# DIYTIL311_v1_2.net
KiCad netlist of a schematic drawn in EAGLE
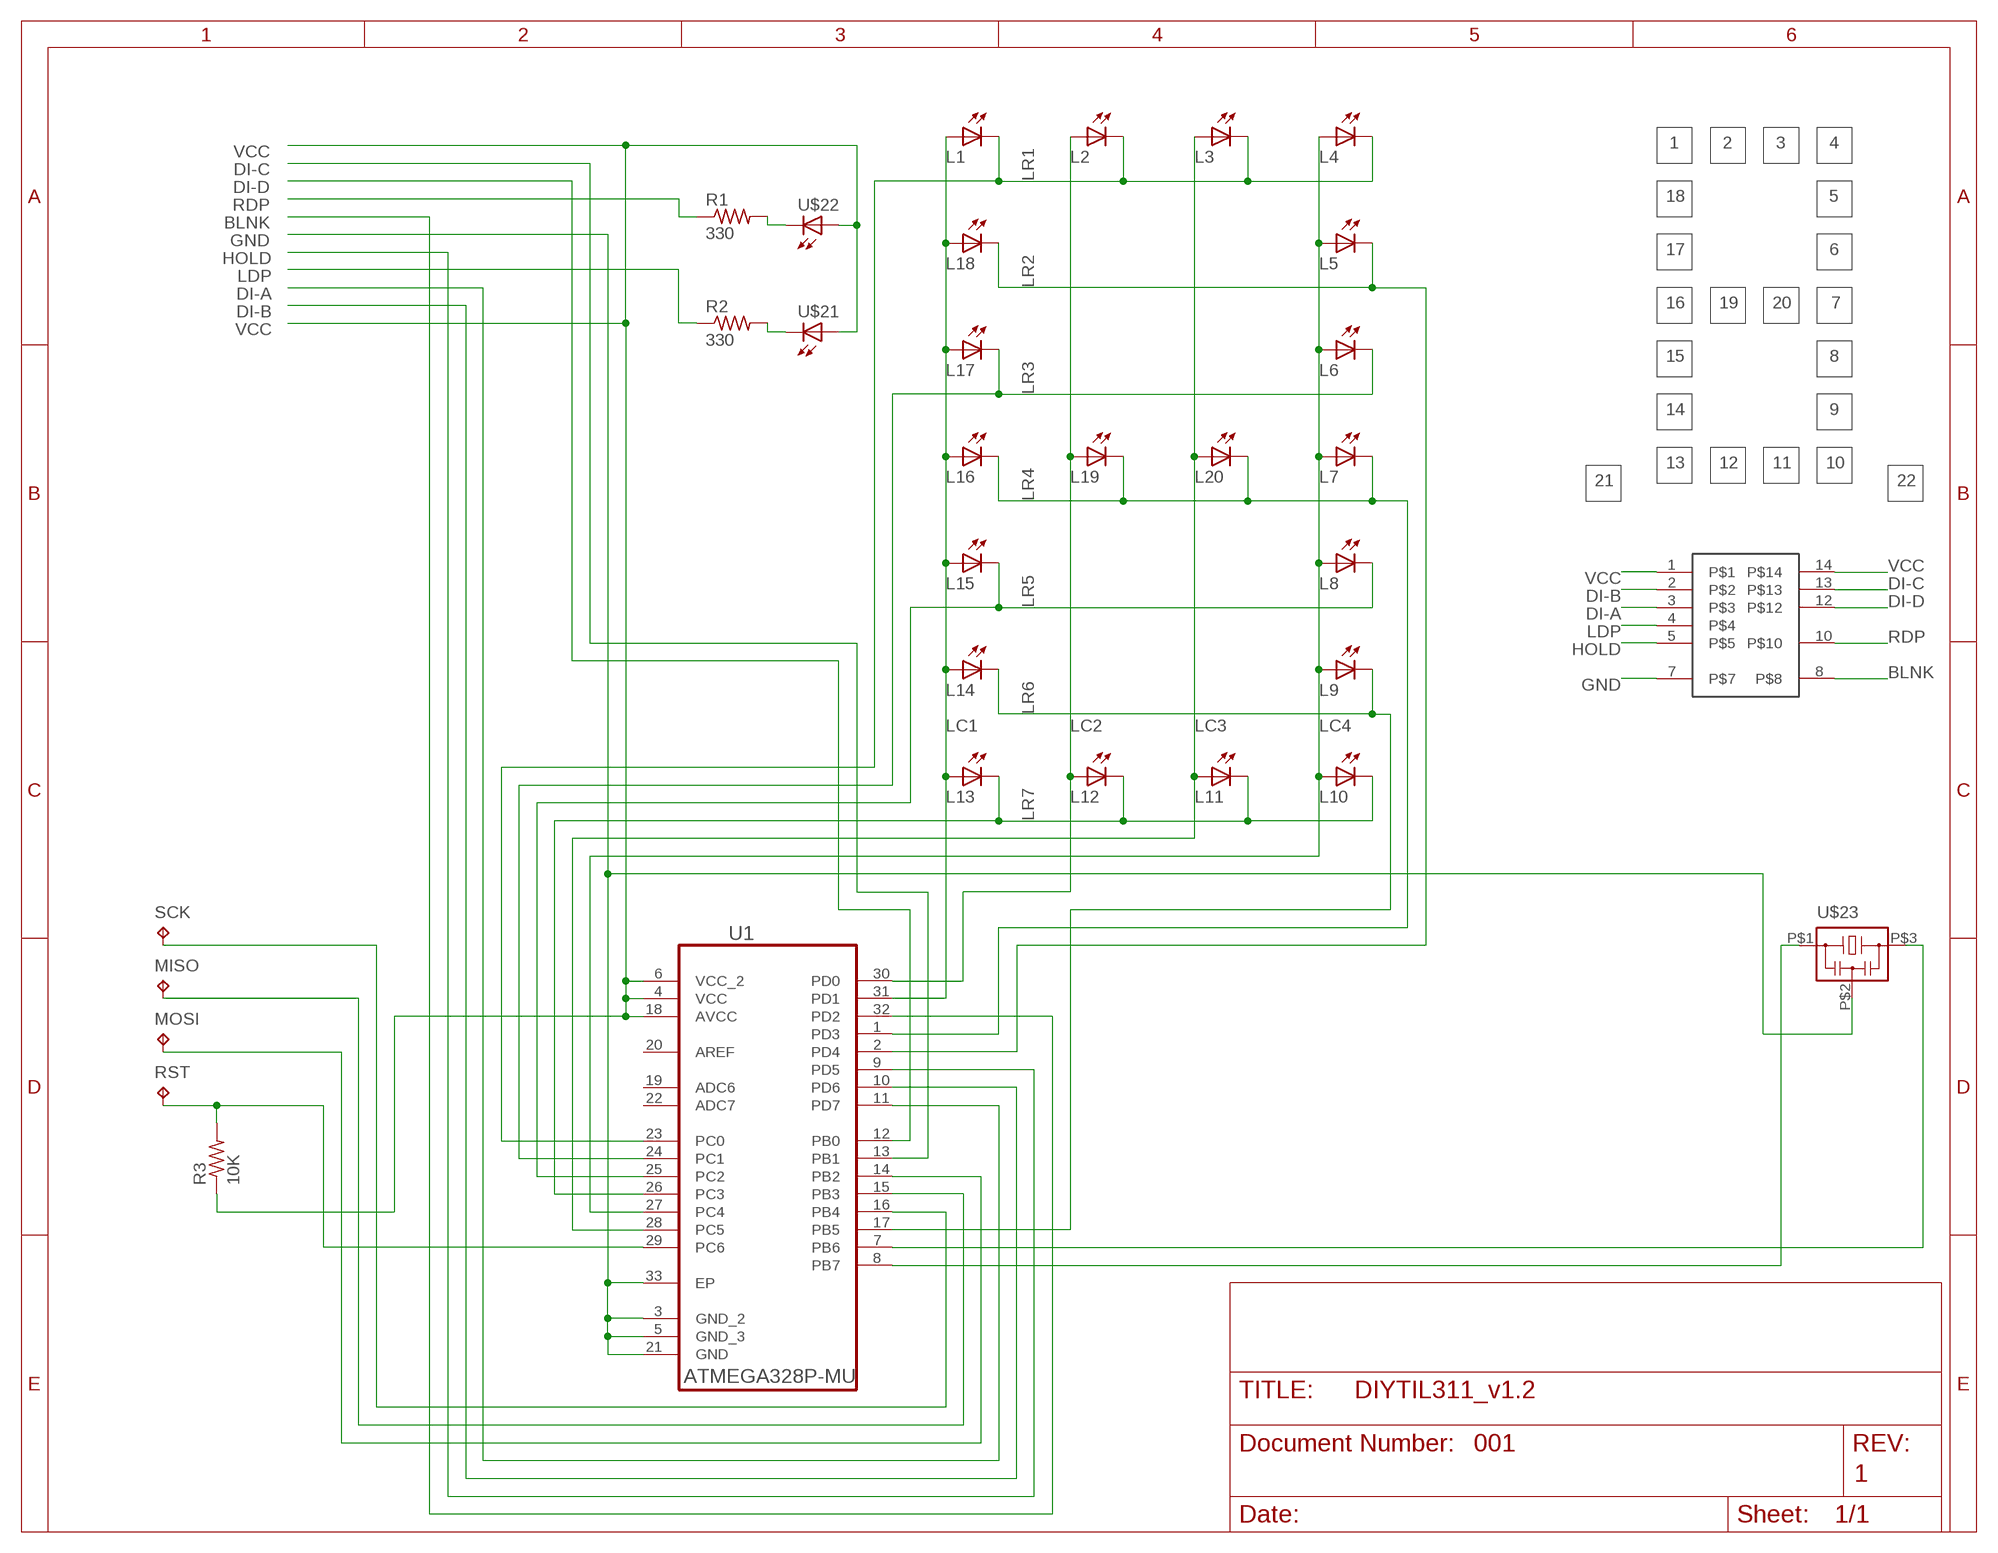
[diagram p0: schematic, sheet 1]

(export (version "E")
  (design (tool "Eeschema 10.0.6"))
  (components
    (comp (ref "L1")
      (value "0201.LED0201")
      (footprint "eagle-import:LEDC0603X33")
      (libsource (lib "eagle-import") (part "0201.LED0201"))
    )
    (comp (ref "L2")
      (value "0201.LED0201")
      (footprint "eagle-import:LEDC0603X33")
      (libsource (lib "eagle-import") (part "0201.LED0201"))
    )
    (comp (ref "L3")
      (value "0201.LED0201")
      (footprint "eagle-import:LEDC0603X33")
      (libsource (lib "eagle-import") (part "0201.LED0201"))
    )
    (comp (ref "L4")
      (value "0201.LED0201")
      (footprint "eagle-import:LEDC0603X33")
      (libsource (lib "eagle-import") (part "0201.LED0201"))
    )
    (comp (ref "L5")
      (value "0201.LED0201")
      (footprint "eagle-import:LEDC0603X33")
      (libsource (lib "eagle-import") (part "0201.LED0201"))
    )
    (comp (ref "L6")
      (value "0201.LED0201")
      (footprint "eagle-import:LEDC0603X33")
      (libsource (lib "eagle-import") (part "0201.LED0201"))
    )
    (comp (ref "L7")
      (value "0201.LED0201")
      (footprint "eagle-import:LEDC0603X33")
      (libsource (lib "eagle-import") (part "0201.LED0201"))
    )
    (comp (ref "L8")
      (value "0201.LED0201")
      (footprint "eagle-import:LEDC0603X33")
      (libsource (lib "eagle-import") (part "0201.LED0201"))
    )
    (comp (ref "L9")
      (value "0201.LED0201")
      (footprint "eagle-import:LEDC0603X33")
      (libsource (lib "eagle-import") (part "0201.LED0201"))
    )
    (comp (ref "L10")
      (value "0201.LED0201")
      (footprint "eagle-import:LEDC0603X33")
      (libsource (lib "eagle-import") (part "0201.LED0201"))
    )
    (comp (ref "L11")
      (value "0201.LED0201")
      (footprint "eagle-import:LEDC0603X33")
      (libsource (lib "eagle-import") (part "0201.LED0201"))
    )
    (comp (ref "L12")
      (value "0201.LED0201")
      (footprint "eagle-import:LEDC0603X33")
      (libsource (lib "eagle-import") (part "0201.LED0201"))
    )
    (comp (ref "L13")
      (value "0201.LED0201")
      (footprint "eagle-import:LEDC0603X33")
      (libsource (lib "eagle-import") (part "0201.LED0201"))
    )
    (comp (ref "L14")
      (value "0201.LED0201")
      (footprint "eagle-import:LEDC0603X33")
      (libsource (lib "eagle-import") (part "0201.LED0201"))
    )
    (comp (ref "L15")
      (value "0201.LED0201")
      (footprint "eagle-import:LEDC0603X33")
      (libsource (lib "eagle-import") (part "0201.LED0201"))
    )
    (comp (ref "L16")
      (value "0201.LED0201")
      (footprint "eagle-import:LEDC0603X33")
      (libsource (lib "eagle-import") (part "0201.LED0201"))
    )
    (comp (ref "L17")
      (value "0201.LED0201")
      (footprint "eagle-import:LEDC0603X33")
      (libsource (lib "eagle-import") (part "0201.LED0201"))
    )
    (comp (ref "L18")
      (value "0201.LED0201")
      (footprint "eagle-import:LEDC0603X33")
      (libsource (lib "eagle-import") (part "0201.LED0201"))
    )
    (comp (ref "L19")
      (value "0201.LED0201")
      (footprint "eagle-import:LEDC0603X33")
      (libsource (lib "eagle-import") (part "0201.LED0201"))
    )
    (comp (ref "L20")
      (value "0201.LED0201")
      (footprint "eagle-import:LEDC0603X33")
      (libsource (lib "eagle-import") (part "0201.LED0201"))
    )
    (comp (ref "MISO")
      (value "TPB1,27")
      (footprint "eagle-import:B1,27")
      (libsource (lib "eagle-import") (part "TPB1,27"))
    )
    (comp (ref "MOSI")
      (value "TPB1,27")
      (footprint "eagle-import:B1,27")
      (libsource (lib "eagle-import") (part "TPB1,27"))
    )
    (comp (ref "R1")
      (value "330")
      (footprint "eagle-import:R0201")
      (libsource (lib "eagle-import") (part "R-US_R0201"))
    )
    (comp (ref "R2")
      (value "330")
      (footprint "eagle-import:R0201")
      (libsource (lib "eagle-import") (part "R-US_R0201"))
    )
    (comp (ref "R3")
      (value "10K")
      (footprint "eagle-import:R0201")
      (libsource (lib "eagle-import") (part "R-US_R0201"))
    )
    (comp (ref "RST")
      (value "TPB1,27")
      (footprint "eagle-import:B1,27")
      (libsource (lib "eagle-import") (part "TPB1,27"))
    )
    (comp (ref "SCK")
      (value "TPB1,27")
      (footprint "eagle-import:B1,27")
      (libsource (lib "eagle-import") (part "TPB1,27"))
    )
    (comp (ref "U$21")
      (value "0201.LED0201")
      (footprint "eagle-import:LEDC0603X33")
      (libsource (lib "eagle-import") (part "0201.LED0201"))
    )
    (comp (ref "U$22")
      (value "0201.LED0201")
      (footprint "eagle-import:LEDC0603X33")
      (libsource (lib "eagle-import") (part "0201.LED0201"))
    )
    (comp (ref "U$23")
      (value "CSTNE16M0V53Z000R0")
      (footprint "eagle-import:MFF")
      (libsource (lib "eagle-import") (part "CSTNE16M0V53Z000R0"))
    )
    (comp (ref "U$24")
      (value "TIL311DIP")
      (footprint "eagle-import:TIL311DIP_FOOTPRINT")
      (libsource (lib "eagle-import") (part "TIL311DIP"))
    )
    (comp (ref "U1")
      (value "ATMEGA328P-MU")
      (footprint "eagle-import:QFN50P500X500X100-33N")
      (libsource (lib "eagle-import") (part "ATMEGA328P-MU"))
    )
  )
  (nets
    (net (code "1") (name "/BLNK") (class "Default")
      (node (ref "U$24") (pin "8") (pinfunction "P$8_8") (pintype "bidirectional"))
      (node (ref "U1") (pin "32") (pinfunction "PD2_32") (pintype "bidirectional"))
    )
    (net (code "2") (name "/DI-A") (class "Default")
      (node (ref "U$24") (pin "3") (pinfunction "P$3_3") (pintype "bidirectional"))
      (node (ref "U1") (pin "11") (pinfunction "PD7_11") (pintype "bidirectional"))
    )
    (net (code "3") (name "/DI-B") (class "Default")
      (node (ref "U$24") (pin "2") (pinfunction "P$2_2") (pintype "bidirectional"))
      (node (ref "U1") (pin "10") (pinfunction "PD6_10") (pintype "bidirectional"))
    )
    (net (code "4") (name "/DI-C") (class "Default")
      (node (ref "U$24") (pin "13") (pinfunction "P$13_13") (pintype "bidirectional"))
      (node (ref "U1") (pin "13") (pinfunction "PB1_13") (pintype "bidirectional"))
    )
    (net (code "5") (name "/DI-D") (class "Default")
      (node (ref "U$24") (pin "12") (pinfunction "P$12_12") (pintype "bidirectional"))
      (node (ref "U1") (pin "12") (pinfunction "PB0_12") (pintype "bidirectional"))
    )
    (net (code "6") (name "/GND") (class "Default")
      (node (ref "U$23") (pin "P$2") (pinfunction "2_P$2") (pintype "passive"))
      (node (ref "U$24") (pin "7") (pinfunction "P$7_7") (pintype "bidirectional"))
      (node (ref "U1") (pin "21") (pinfunction "GND_21") (pintype "passive"))
      (node (ref "U1") (pin "3") (pinfunction "GND_2_3") (pintype "passive"))
      (node (ref "U1") (pin "33") (pinfunction "EP_33") (pintype "passive"))
      (node (ref "U1") (pin "5") (pinfunction "GND_3_5") (pintype "passive"))
    )
    (net (code "7") (name "/HOLD") (class "Default")
      (node (ref "U$24") (pin "5") (pinfunction "P$5_5") (pintype "bidirectional"))
      (node (ref "U1") (pin "9") (pinfunction "PD5_9") (pintype "bidirectional"))
    )
    (net (code "8") (name "/LC1") (class "Default")
      (node (ref "L1") (pin "1") (pinfunction "A_1") (pintype "passive"))
      (node (ref "L13") (pin "1") (pinfunction "A_1") (pintype "passive"))
      (node (ref "L14") (pin "1") (pinfunction "A_1") (pintype "passive"))
      (node (ref "L15") (pin "1") (pinfunction "A_1") (pintype "passive"))
      (node (ref "L16") (pin "1") (pinfunction "A_1") (pintype "passive"))
      (node (ref "L17") (pin "1") (pinfunction "A_1") (pintype "passive"))
      (node (ref "L18") (pin "1") (pinfunction "A_1") (pintype "passive"))
      (node (ref "U1") (pin "31") (pinfunction "PD1_31") (pintype "bidirectional"))
    )
    (net (code "9") (name "/LC2") (class "Default")
      (node (ref "L12") (pin "1") (pinfunction "A_1") (pintype "passive"))
      (node (ref "L19") (pin "1") (pinfunction "A_1") (pintype "passive"))
      (node (ref "L2") (pin "1") (pinfunction "A_1") (pintype "passive"))
      (node (ref "U1") (pin "30") (pinfunction "PD0_30") (pintype "bidirectional"))
    )
    (net (code "10") (name "/LC3") (class "Default")
      (node (ref "L11") (pin "1") (pinfunction "A_1") (pintype "passive"))
      (node (ref "L20") (pin "1") (pinfunction "A_1") (pintype "passive"))
      (node (ref "L3") (pin "1") (pinfunction "A_1") (pintype "passive"))
      (node (ref "U1") (pin "28") (pinfunction "PC5_28") (pintype "bidirectional"))
    )
    (net (code "11") (name "/LC4") (class "Default")
      (node (ref "L10") (pin "1") (pinfunction "A_1") (pintype "passive"))
      (node (ref "L4") (pin "1") (pinfunction "A_1") (pintype "passive"))
      (node (ref "L5") (pin "1") (pinfunction "A_1") (pintype "passive"))
      (node (ref "L6") (pin "1") (pinfunction "A_1") (pintype "passive"))
      (node (ref "L7") (pin "1") (pinfunction "A_1") (pintype "passive"))
      (node (ref "L8") (pin "1") (pinfunction "A_1") (pintype "passive"))
      (node (ref "L9") (pin "1") (pinfunction "A_1") (pintype "passive"))
      (node (ref "U1") (pin "27") (pinfunction "PC4_27") (pintype "bidirectional"))
    )
    (net (code "12") (name "/LDP") (class "Default")
      (node (ref "R2") (pin "1") (pinfunction "1_1") (pintype "passive"))
      (node (ref "U$24") (pin "4") (pinfunction "P$4_4") (pintype "bidirectional"))
    )
    (net (code "13") (name "/LR1") (class "Default")
      (node (ref "L1") (pin "2") (pinfunction "C_2") (pintype "passive"))
      (node (ref "L2") (pin "2") (pinfunction "C_2") (pintype "passive"))
      (node (ref "L3") (pin "2") (pinfunction "C_2") (pintype "passive"))
      (node (ref "L4") (pin "2") (pinfunction "C_2") (pintype "passive"))
      (node (ref "U1") (pin "23") (pinfunction "PC0_23") (pintype "bidirectional"))
    )
    (net (code "14") (name "/LR2") (class "Default")
      (node (ref "L18") (pin "2") (pinfunction "C_2") (pintype "passive"))
      (node (ref "L5") (pin "2") (pinfunction "C_2") (pintype "passive"))
      (node (ref "U1") (pin "2") (pinfunction "PD4_2") (pintype "bidirectional"))
    )
    (net (code "15") (name "/LR3") (class "Default")
      (node (ref "L17") (pin "2") (pinfunction "C_2") (pintype "passive"))
      (node (ref "L6") (pin "2") (pinfunction "C_2") (pintype "passive"))
      (node (ref "U1") (pin "24") (pinfunction "PC1_24") (pintype "bidirectional"))
    )
    (net (code "16") (name "/LR4") (class "Default")
      (node (ref "L16") (pin "2") (pinfunction "C_2") (pintype "passive"))
      (node (ref "L19") (pin "2") (pinfunction "C_2") (pintype "passive"))
      (node (ref "L20") (pin "2") (pinfunction "C_2") (pintype "passive"))
      (node (ref "L7") (pin "2") (pinfunction "C_2") (pintype "passive"))
      (node (ref "U1") (pin "1") (pinfunction "PD3_1") (pintype "bidirectional"))
    )
    (net (code "17") (name "/LR5") (class "Default")
      (node (ref "L15") (pin "2") (pinfunction "C_2") (pintype "passive"))
      (node (ref "L8") (pin "2") (pinfunction "C_2") (pintype "passive"))
      (node (ref "U1") (pin "25") (pinfunction "PC2_25") (pintype "bidirectional"))
    )
    (net (code "18") (name "/LR6") (class "Default")
      (node (ref "L14") (pin "2") (pinfunction "C_2") (pintype "passive"))
      (node (ref "L9") (pin "2") (pinfunction "C_2") (pintype "passive"))
      (node (ref "U1") (pin "17") (pinfunction "PB5_17") (pintype "bidirectional"))
    )
    (net (code "19") (name "/LR7") (class "Default")
      (node (ref "L10") (pin "2") (pinfunction "C_2") (pintype "passive"))
      (node (ref "L11") (pin "2") (pinfunction "C_2") (pintype "passive"))
      (node (ref "L12") (pin "2") (pinfunction "C_2") (pintype "passive"))
      (node (ref "L13") (pin "2") (pinfunction "C_2") (pintype "passive"))
      (node (ref "U1") (pin "26") (pinfunction "PC3_26") (pintype "bidirectional"))
    )
    (net (code "20") (name "/RDP") (class "Default")
      (node (ref "R1") (pin "1") (pinfunction "1_1") (pintype "passive"))
      (node (ref "U$24") (pin "10") (pinfunction "P$10_10") (pintype "bidirectional"))
    )
    (net (code "21") (name "/VCC") (class "Default")
      (node (ref "R3") (pin "1") (pinfunction "1_1") (pintype "passive"))
      (node (ref "U$21") (pin "1") (pinfunction "A_1") (pintype "passive"))
      (node (ref "U$22") (pin "1") (pinfunction "A_1") (pintype "passive"))
      (node (ref "U$24") (pin "1") (pinfunction "P$1_1") (pintype "bidirectional"))
      (node (ref "U$24") (pin "14") (pinfunction "P$14_14") (pintype "bidirectional"))
      (node (ref "U1") (pin "18") (pinfunction "AVCC_18") (pintype "power_in"))
      (node (ref "U1") (pin "4") (pinfunction "VCC_4") (pintype "power_in"))
      (node (ref "U1") (pin "6") (pinfunction "VCC_2_6") (pintype "power_in"))
    )
    (net (code "22") (name "Net-(U$21-C)") (class "Default")
      (node (ref "R2") (pin "2") (pinfunction "2_2") (pintype "passive"))
      (node (ref "U$21") (pin "2") (pinfunction "C_2") (pintype "passive"))
    )
    (net (code "23") (name "Net-(U$22-C)") (class "Default")
      (node (ref "R1") (pin "2") (pinfunction "2_2") (pintype "passive"))
      (node (ref "U$22") (pin "2") (pinfunction "C_2") (pintype "passive"))
    )
    (net (code "24") (name "Net-(U$23-1)") (class "Default")
      (node (ref "U$23") (pin "P$1") (pinfunction "1_P$1") (pintype "passive"))
      (node (ref "U1") (pin "8") (pinfunction "PB7_8") (pintype "bidirectional"))
    )
    (net (code "25") (name "Net-(U$23-3)") (class "Default")
      (node (ref "U$23") (pin "P$3") (pinfunction "3_P$3") (pintype "passive"))
      (node (ref "U1") (pin "7") (pinfunction "PB6_7") (pintype "bidirectional"))
    )
    (net (code "26") (name "Net-(U1-PB2)") (class "Default")
      (node (ref "MOSI") (pin "TP") (pinfunction "TP_TP") (pintype "input"))
      (node (ref "U1") (pin "14") (pinfunction "PB2_14") (pintype "bidirectional"))
    )
    (net (code "27") (name "Net-(U1-PB3)") (class "Default")
      (node (ref "MISO") (pin "TP") (pinfunction "TP_TP") (pintype "input"))
      (node (ref "U1") (pin "15") (pinfunction "PB3_15") (pintype "bidirectional"))
    )
    (net (code "28") (name "Net-(U1-PB4)") (class "Default")
      (node (ref "SCK") (pin "TP") (pinfunction "TP_TP") (pintype "input"))
      (node (ref "U1") (pin "16") (pinfunction "PB4_16") (pintype "bidirectional"))
    )
    (net (code "29") (name "Net-(U1-PC6)") (class "Default")
      (node (ref "R3") (pin "2") (pinfunction "2_2") (pintype "passive"))
      (node (ref "RST") (pin "TP") (pinfunction "TP_TP") (pintype "input"))
      (node (ref "U1") (pin "29") (pinfunction "PC6_29") (pintype "bidirectional"))
    )
    (net (code "30") (name "unconnected-(U1-ADC6-Pad19)") (class "Default")
      (node (ref "U1") (pin "19") (pinfunction "ADC6_19") (pintype "input"))
    )
    (net (code "31") (name "unconnected-(U1-ADC7-Pad22)") (class "Default")
      (node (ref "U1") (pin "22") (pinfunction "ADC7_22") (pintype "input"))
    )
    (net (code "32") (name "unconnected-(U1-AREF-Pad20)") (class "Default")
      (node (ref "U1") (pin "20") (pinfunction "AREF_20") (pintype "input"))
    )
  )
)
